# Smarttree_CMU_5_2_3.net
KiCad netlist of a schematic drawn in EAGLE
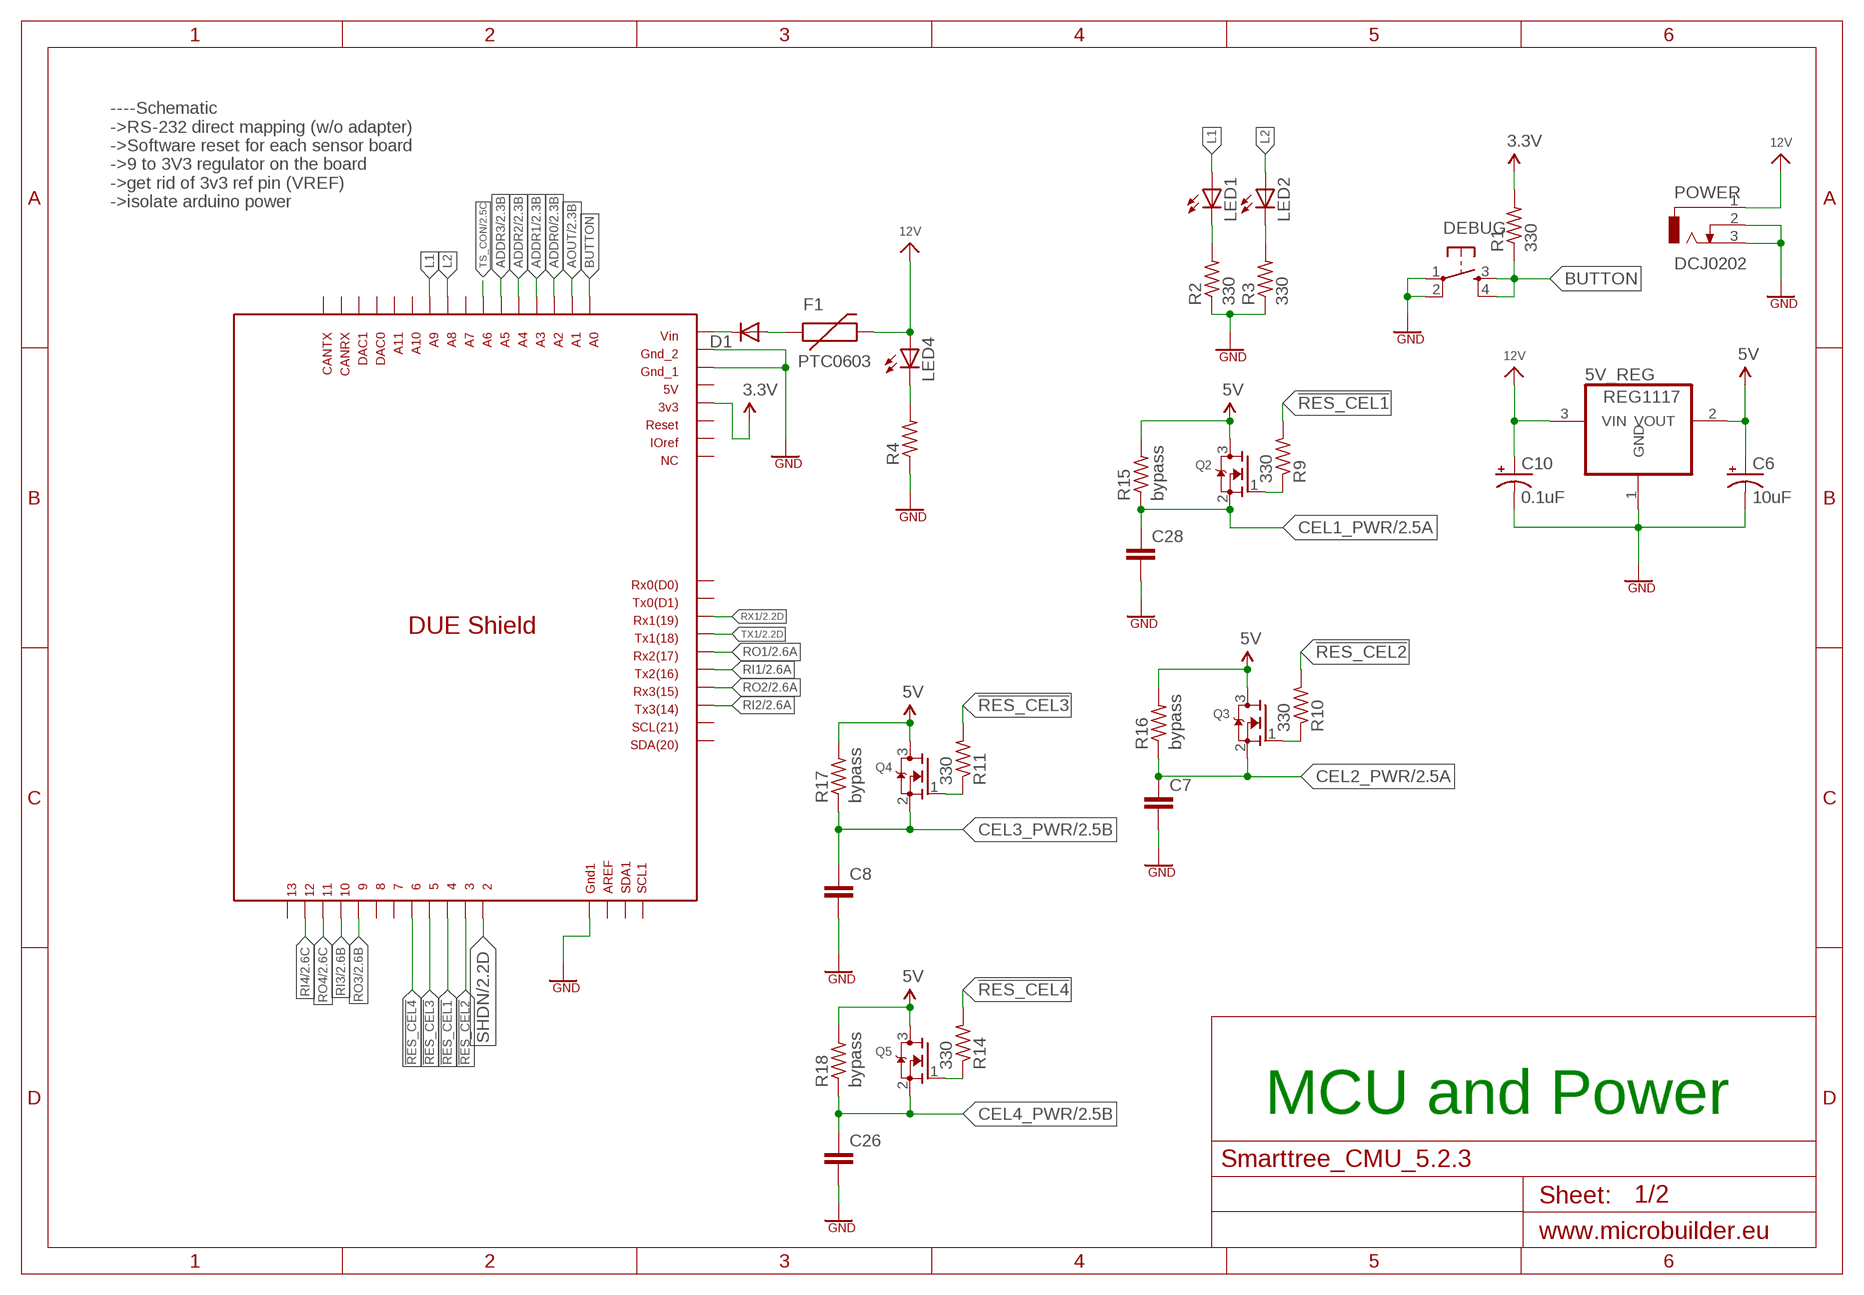
[diagram p0: schematic, sheet 1]
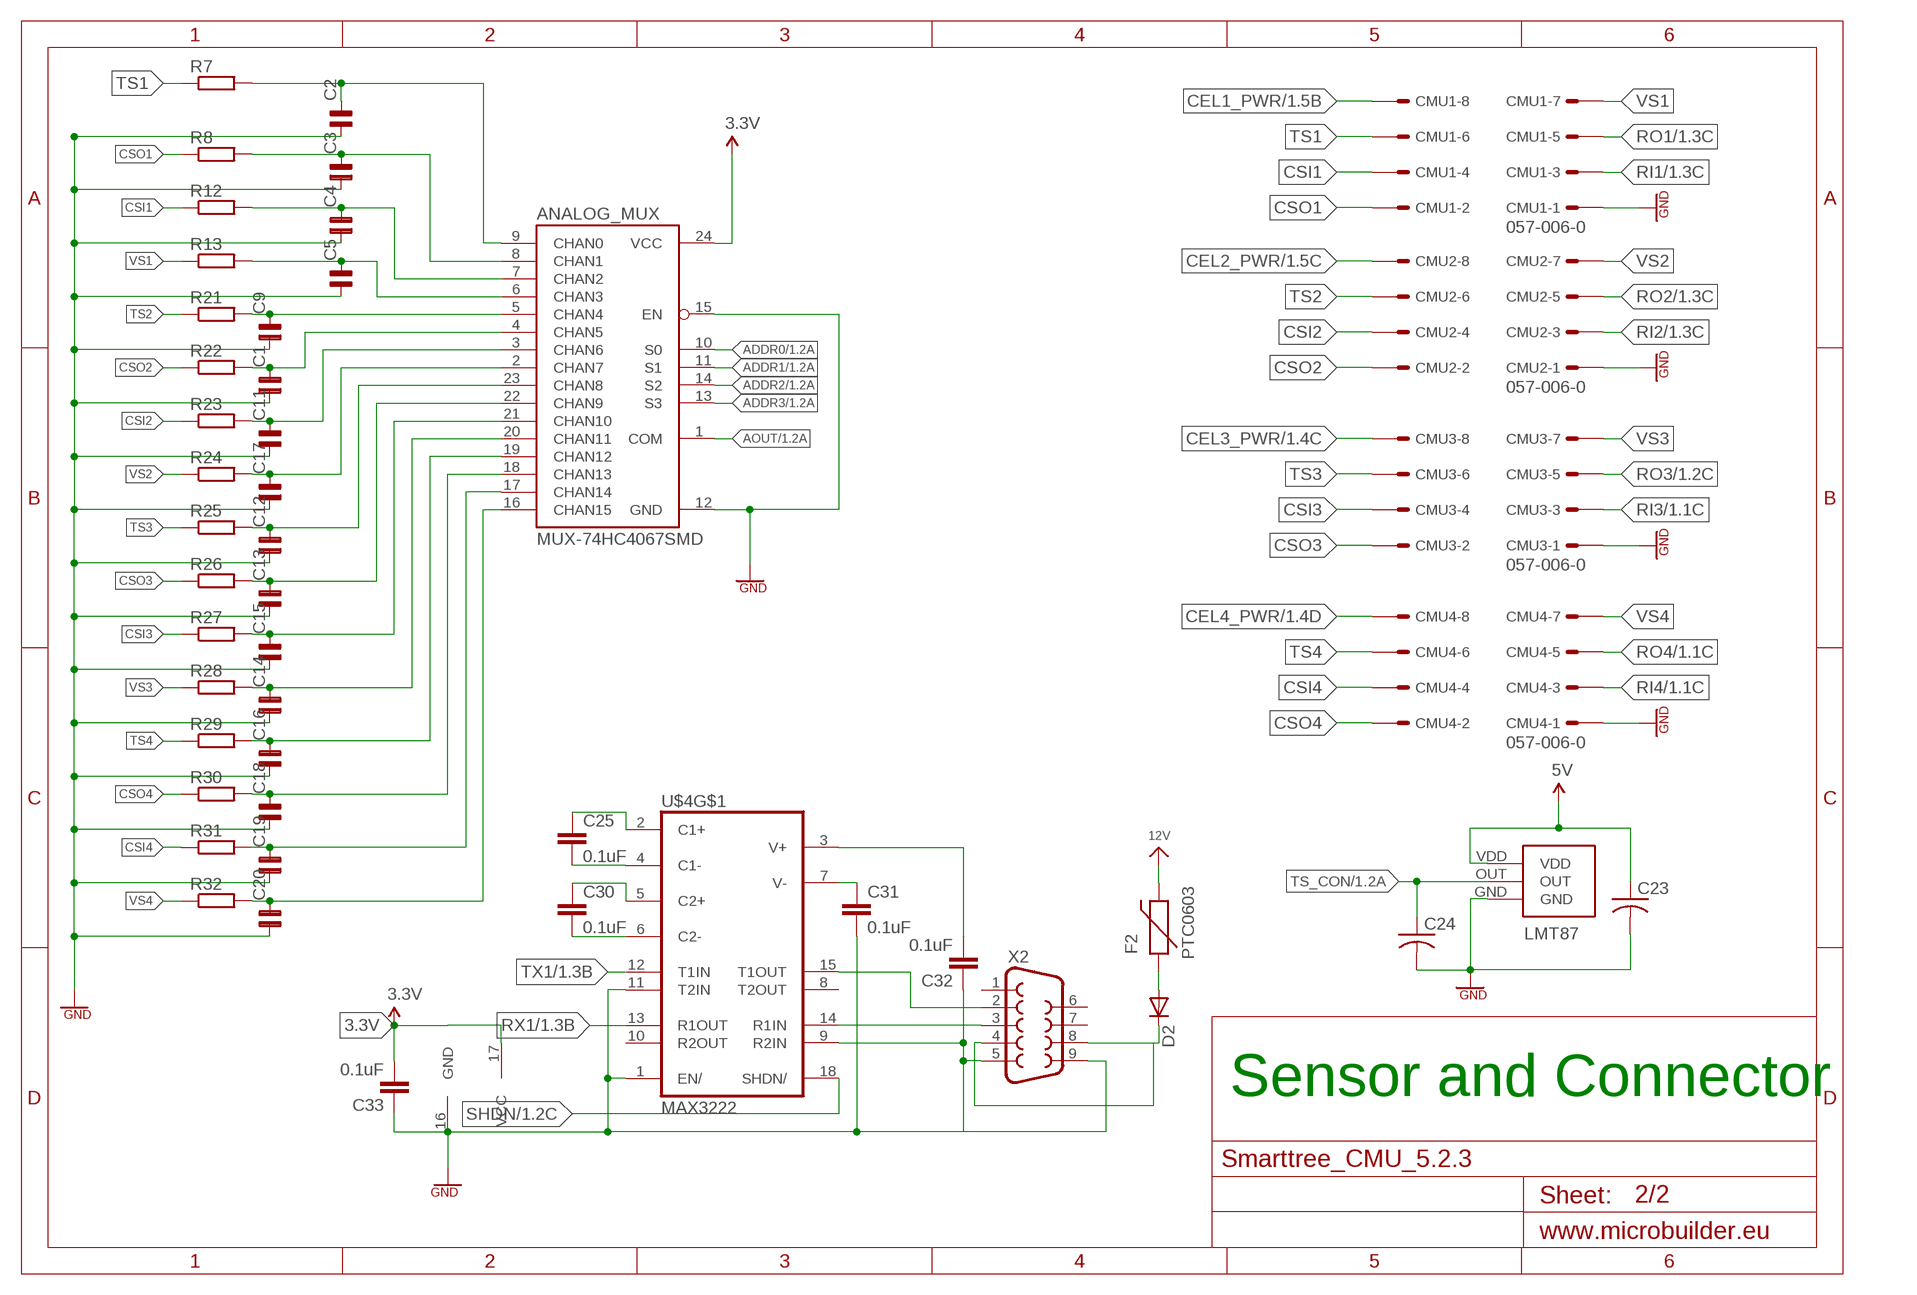
[diagram p1: schematic, sheet 2]

(export (version "E")
  (design (tool "Eeschema 10.0.6"))
  (components
    (comp (ref "5V_REG")
      (value "REG1117")
      (footprint "eagle-import:SOT223")
      (libsource (lib "eagle-import") (part "REG1117"))
    )
    (comp (ref "C6")
      (value "10uF")
      (footprint "eagle-import:EIA3216")
      (libsource (lib "eagle-import") (part "10UF-TANT"))
    )
    (comp (ref "C7")
      (value "CAP0603-CAP")
      (footprint "eagle-import:0603-CAP")
      (libsource (lib "eagle-import") (part "CAP0603-CAP"))
    )
    (comp (ref "C8")
      (value "CAP0603-CAP")
      (footprint "eagle-import:0603-CAP")
      (libsource (lib "eagle-import") (part "CAP0603-CAP"))
    )
    (comp (ref "C10")
      (value "0.1uF")
      (footprint "eagle-import:EIA3216")
      (libsource (lib "eagle-import") (part "10UF-TANT"))
    )
    (comp (ref "C26")
      (value "CAP0603-CAP")
      (footprint "eagle-import:0603-CAP")
      (libsource (lib "eagle-import") (part "CAP0603-CAP"))
    )
    (comp (ref "C28")
      (value "CAP0603-CAP")
      (footprint "eagle-import:0603-CAP")
      (libsource (lib "eagle-import") (part "CAP0603-CAP"))
    )
    (comp (ref "D1")
      (value "DIODE-SOD106-R")
      (footprint "eagle-import:SOD106-R")
      (libsource (lib "eagle-import") (part "DIODE-SOD106-R"))
    )
    (comp (ref "DEBUG")
      (value "TAC_SWITCHSMD")
      (footprint "eagle-import:TACTILE_SWITCH_SMD")
      (libsource (lib "eagle-import") (part "TAC_SWITCHSMD"))
    )
    (comp (ref "F1")
      (value "PTC0603")
      (footprint "eagle-import:0603")
      (libsource (lib "eagle-import") (part "PTC0603"))
    )
    (comp (ref "LED1")
      (value "LED-YELLOW0603")
      (footprint "eagle-import:LED-0603")
      (libsource (lib "eagle-import") (part "LED-YELLOW0603"))
    )
    (comp (ref "LED2")
      (value "LED-YELLOW0603")
      (footprint "eagle-import:LED-0603")
      (libsource (lib "eagle-import") (part "LED-YELLOW0603"))
    )
    (comp (ref "LED4")
      (value "LED-YELLOW0603")
      (footprint "eagle-import:LED-0603")
      (libsource (lib "eagle-import") (part "LED-YELLOW0603"))
    )
    (comp (ref "POWER")
      (value "DCJ0202")
      (footprint "eagle-import:DCJ0202")
      (libsource (lib "eagle-import") (part "DCJ0202"))
    )
    (comp (ref "Q2")
      (value "MOSFET-NREFLOW")
      (footprint "eagle-import:SOT23")
      (libsource (lib "eagle-import") (part "MOSFET-NREFLOW"))
    )
    (comp (ref "Q3")
      (value "MOSFET-NREFLOW")
      (footprint "eagle-import:SOT23")
      (libsource (lib "eagle-import") (part "MOSFET-NREFLOW"))
    )
    (comp (ref "Q4")
      (value "MOSFET-NREFLOW")
      (footprint "eagle-import:SOT23")
      (libsource (lib "eagle-import") (part "MOSFET-NREFLOW"))
    )
    (comp (ref "Q5")
      (value "MOSFET-NREFLOW")
      (footprint "eagle-import:SOT23")
      (libsource (lib "eagle-import") (part "MOSFET-NREFLOW"))
    )
    (comp (ref "R1")
      (value "330")
      (footprint "eagle-import:M0805")
      (libsource (lib "eagle-import") (part "R-US_M0805"))
    )
    (comp (ref "R2")
      (value "330")
      (footprint "eagle-import:M0805")
      (libsource (lib "eagle-import") (part "R-US_M0805"))
    )
    (comp (ref "R3")
      (value "330")
      (footprint "eagle-import:M0805")
      (libsource (lib "eagle-import") (part "R-US_M0805"))
    )
    (comp (ref "R4")
      (value "R-US_M0805")
      (footprint "eagle-import:M0805")
      (libsource (lib "eagle-import") (part "R-US_M0805"))
    )
    (comp (ref "R9")
      (value "330")
      (footprint "eagle-import:R0805")
      (libsource (lib "eagle-import") (part "R-US_R0805"))
    )
    (comp (ref "R10")
      (value "330")
      (footprint "eagle-import:R0805")
      (libsource (lib "eagle-import") (part "R-US_R0805"))
    )
    (comp (ref "R11")
      (value "330")
      (footprint "eagle-import:R0805")
      (libsource (lib "eagle-import") (part "R-US_R0805"))
    )
    (comp (ref "R14")
      (value "330")
      (footprint "eagle-import:R0805")
      (libsource (lib "eagle-import") (part "R-US_R0805"))
    )
    (comp (ref "R15")
      (value "bypass")
      (footprint "eagle-import:M0805")
      (libsource (lib "eagle-import") (part "R-US_M0805"))
    )
    (comp (ref "R16")
      (value "bypass")
      (footprint "eagle-import:M0805")
      (libsource (lib "eagle-import") (part "R-US_M0805"))
    )
    (comp (ref "R17")
      (value "bypass")
      (footprint "eagle-import:M0805")
      (libsource (lib "eagle-import") (part "R-US_M0805"))
    )
    (comp (ref "R18")
      (value "bypass")
      (footprint "eagle-import:M0805")
      (libsource (lib "eagle-import") (part "R-US_M0805"))
    )
    (comp (ref "U$1")
      (value "DUE(OUTLINE)")
      (footprint "eagle-import:DUE(NORMAL)")
      (libsource (lib "eagle-import") (part "DUE(OUTLINE)"))
    )
    (comp (ref "ANALOG_MUX")
      (value "MUX-74HC4067SMD")
      (footprint "eagle-import:SSOP24")
      (libsource (lib "eagle-import") (part "MUX-74HC4067SMD"))
    )
    (comp (ref "C1")
      (value "C-NP-SMD-0805")
      (footprint "eagle-import:C-0805")
      (libsource (lib "eagle-import") (part "C-NP-SMD-0805"))
    )
    (comp (ref "C2")
      (value "C-NP-SMD-0805")
      (footprint "eagle-import:C-0805")
      (libsource (lib "eagle-import") (part "C-NP-SMD-0805"))
    )
    (comp (ref "C3")
      (value "C-NP-SMD-0805")
      (footprint "eagle-import:C-0805")
      (libsource (lib "eagle-import") (part "C-NP-SMD-0805"))
    )
    (comp (ref "C4")
      (value "C-NP-SMD-0805")
      (footprint "eagle-import:C-0805")
      (libsource (lib "eagle-import") (part "C-NP-SMD-0805"))
    )
    (comp (ref "C5")
      (value "C-NP-SMD-0805")
      (footprint "eagle-import:C-0805")
      (libsource (lib "eagle-import") (part "C-NP-SMD-0805"))
    )
    (comp (ref "C9")
      (value "C-NP-SMD-0805")
      (footprint "eagle-import:C-0805")
      (libsource (lib "eagle-import") (part "C-NP-SMD-0805"))
    )
    (comp (ref "C11")
      (value "C-NP-SMD-0805")
      (footprint "eagle-import:C-0805")
      (libsource (lib "eagle-import") (part "C-NP-SMD-0805"))
    )
    (comp (ref "C12")
      (value "C-NP-SMD-0805")
      (footprint "eagle-import:C-0805")
      (libsource (lib "eagle-import") (part "C-NP-SMD-0805"))
    )
    (comp (ref "C13")
      (value "C-NP-SMD-0805")
      (footprint "eagle-import:C-0805")
      (libsource (lib "eagle-import") (part "C-NP-SMD-0805"))
    )
    (comp (ref "C14")
      (value "C-NP-SMD-0805")
      (footprint "eagle-import:C-0805")
      (libsource (lib "eagle-import") (part "C-NP-SMD-0805"))
    )
    (comp (ref "C15")
      (value "C-NP-SMD-0805")
      (footprint "eagle-import:C-0805")
      (libsource (lib "eagle-import") (part "C-NP-SMD-0805"))
    )
    (comp (ref "C16")
      (value "C-NP-SMD-0805")
      (footprint "eagle-import:C-0805")
      (libsource (lib "eagle-import") (part "C-NP-SMD-0805"))
    )
    (comp (ref "C17")
      (value "C-NP-SMD-0805")
      (footprint "eagle-import:C-0805")
      (libsource (lib "eagle-import") (part "C-NP-SMD-0805"))
    )
    (comp (ref "C18")
      (value "C-NP-SMD-0805")
      (footprint "eagle-import:C-0805")
      (libsource (lib "eagle-import") (part "C-NP-SMD-0805"))
    )
    (comp (ref "C19")
      (value "C-NP-SMD-0805")
      (footprint "eagle-import:C-0805")
      (libsource (lib "eagle-import") (part "C-NP-SMD-0805"))
    )
    (comp (ref "C20")
      (value "C-NP-SMD-0805")
      (footprint "eagle-import:C-0805")
      (libsource (lib "eagle-import") (part "C-NP-SMD-0805"))
    )
    (comp (ref "C23")
      (value "C-USC0805")
      (footprint "eagle-import:C0805")
      (libsource (lib "eagle-import") (part "C-USC0805"))
    )
    (comp (ref "C24")
      (value "C-USC0805")
      (footprint "eagle-import:C0805")
      (libsource (lib "eagle-import") (part "C-USC0805"))
    )
    (comp (ref "C25")
      (value "0.1uF")
      (footprint "eagle-import:0603-CAP")
      (libsource (lib "eagle-import") (part "CAP0603-CAP"))
    )
    (comp (ref "C30")
      (value "0.1uF")
      (footprint "eagle-import:0603-CAP")
      (libsource (lib "eagle-import") (part "CAP0603-CAP"))
    )
    (comp (ref "C31")
      (value "0.1uF")
      (footprint "eagle-import:0603-CAP")
      (libsource (lib "eagle-import") (part "CAP0603-CAP"))
    )
    (comp (ref "C32")
      (value "0.1uF")
      (footprint "eagle-import:0603-CAP")
      (libsource (lib "eagle-import") (part "CAP0603-CAP"))
    )
    (comp (ref "C33")
      (value "0.1uF")
      (footprint "eagle-import:0603-CAP")
      (libsource (lib "eagle-import") (part "CAP0603-CAP"))
    )
    (comp (ref "CMU1")
      (value "057-006-0")
      (footprint "eagle-import:057-006-0")
      (libsource (lib "eagle-import") (part "057-006-0"))
    )
    (comp (ref "CMU2")
      (value "057-006-0")
      (footprint "eagle-import:057-006-0")
      (libsource (lib "eagle-import") (part "057-006-0"))
    )
    (comp (ref "CMU3")
      (value "057-006-0")
      (footprint "eagle-import:057-006-0")
      (libsource (lib "eagle-import") (part "057-006-0"))
    )
    (comp (ref "CMU4")
      (value "057-006-0")
      (footprint "eagle-import:057-006-0")
      (libsource (lib "eagle-import") (part "057-006-0"))
    )
    (comp (ref "D2")
      (value "DIODE-SOD106-R")
      (footprint "eagle-import:SOD106-R")
      (libsource (lib "eagle-import") (part "DIODE-SOD106-R"))
    )
    (comp (ref "F2")
      (value "PTC0603")
      (footprint "eagle-import:0603")
      (libsource (lib "eagle-import") (part "PTC0603"))
    )
    (comp (ref "LMT87")
      (value "LMT87_PAC")
      (footprint "eagle-import:LMT87_TO")
      (libsource (lib "eagle-import") (part "LMT87_PAC"))
    )
    (comp (ref "R7")
      (value "R-EU_R0805W")
      (footprint "eagle-import:R0805W")
      (libsource (lib "eagle-import") (part "R-EU_R0805W"))
    )
    (comp (ref "R8")
      (value "R-EU_R0805W")
      (footprint "eagle-import:R0805W")
      (libsource (lib "eagle-import") (part "R-EU_R0805W"))
    )
    (comp (ref "R12")
      (value "R-EU_R0805W")
      (footprint "eagle-import:R0805W")
      (libsource (lib "eagle-import") (part "R-EU_R0805W"))
    )
    (comp (ref "R13")
      (value "R-EU_R0805W")
      (footprint "eagle-import:R0805W")
      (libsource (lib "eagle-import") (part "R-EU_R0805W"))
    )
    (comp (ref "R21")
      (value "R-EU_R0805W")
      (footprint "eagle-import:R0805W")
      (libsource (lib "eagle-import") (part "R-EU_R0805W"))
    )
    (comp (ref "R22")
      (value "R-EU_R0805W")
      (footprint "eagle-import:R0805W")
      (libsource (lib "eagle-import") (part "R-EU_R0805W"))
    )
    (comp (ref "R23")
      (value "R-EU_R0805W")
      (footprint "eagle-import:R0805W")
      (libsource (lib "eagle-import") (part "R-EU_R0805W"))
    )
    (comp (ref "R24")
      (value "R-EU_R0805W")
      (footprint "eagle-import:R0805W")
      (libsource (lib "eagle-import") (part "R-EU_R0805W"))
    )
    (comp (ref "R25")
      (value "R-EU_R0805W")
      (footprint "eagle-import:R0805W")
      (libsource (lib "eagle-import") (part "R-EU_R0805W"))
    )
    (comp (ref "R26")
      (value "R-EU_R0805W")
      (footprint "eagle-import:R0805W")
      (libsource (lib "eagle-import") (part "R-EU_R0805W"))
    )
    (comp (ref "R27")
      (value "R-EU_R0805W")
      (footprint "eagle-import:R0805W")
      (libsource (lib "eagle-import") (part "R-EU_R0805W"))
    )
    (comp (ref "R28")
      (value "R-EU_R0805W")
      (footprint "eagle-import:R0805W")
      (libsource (lib "eagle-import") (part "R-EU_R0805W"))
    )
    (comp (ref "R29")
      (value "R-EU_R0805W")
      (footprint "eagle-import:R0805W")
      (libsource (lib "eagle-import") (part "R-EU_R0805W"))
    )
    (comp (ref "R30")
      (value "R-EU_R0805W")
      (footprint "eagle-import:R0805W")
      (libsource (lib "eagle-import") (part "R-EU_R0805W"))
    )
    (comp (ref "R31")
      (value "R-EU_R0805W")
      (footprint "eagle-import:R0805W")
      (libsource (lib "eagle-import") (part "R-EU_R0805W"))
    )
    (comp (ref "R32")
      (value "R-EU_R0805W")
      (footprint "eagle-import:R0805W")
      (libsource (lib "eagle-import") (part "R-EU_R0805W"))
    )
    (comp (ref "U$4")
      (value "MAX3222")
      (footprint "eagle-import:SO18")
      (libsource (lib "eagle-import") (part "MAX3222"))
    )
    (comp (ref "X2")
      (value "DB9MALE")
      (footprint "eagle-import:DB9_MALE")
      (libsource (lib "eagle-import") (part "DB9MALE"))
    )
  )
  (nets
    (net (code "1") (name "3.3V") (class "Default")
      (node (ref "ANALOG_MUX") (pin "24") (pinfunction "VCC_24") (pintype "bidirectional"))
      (node (ref "C33") (pin "2") (pinfunction "2_2") (pintype "passive"))
      (node (ref "R1") (pin "2") (pinfunction "2_2") (pintype "passive"))
      (node (ref "U$1") (pin "3V3") (pinfunction "3V3_3V3") (pintype "bidirectional"))
      (node (ref "U$4") (pin "17") (pinfunction "VCC_17") (pintype "bidirectional"))
    )
    (net (code "2") (name "5V") (class "Default")
      (node (ref "5V_REG") (pin "2") (pinfunction "VOUT_2") (pintype "output"))
      (node (ref "C23") (pin "1") (pinfunction "1_1") (pintype "passive"))
      (node (ref "C6") (pin "A") (pinfunction "+_A") (pintype "passive"))
      (node (ref "LMT87") (pin "VDD") (pinfunction "VDD_VDD") (pintype "bidirectional"))
      (node (ref "Q2") (pin "3") (pinfunction "D_3") (pintype "bidirectional"))
      (node (ref "Q3") (pin "3") (pinfunction "D_3") (pintype "bidirectional"))
      (node (ref "Q4") (pin "3") (pinfunction "D_3") (pintype "bidirectional"))
      (node (ref "Q5") (pin "3") (pinfunction "D_3") (pintype "bidirectional"))
      (node (ref "R15") (pin "2") (pinfunction "2_2") (pintype "passive"))
      (node (ref "R16") (pin "2") (pinfunction "2_2") (pintype "passive"))
      (node (ref "R17") (pin "2") (pinfunction "2_2") (pintype "passive"))
      (node (ref "R18") (pin "2") (pinfunction "2_2") (pintype "passive"))
    )
    (net (code "3") (name "12V") (class "Default")
      (node (ref "5V_REG") (pin "3") (pinfunction "VIN_3") (pintype "input"))
      (node (ref "C10") (pin "A") (pinfunction "+_A") (pintype "passive"))
      (node (ref "F1") (pin "2") (pinfunction "2_2") (pintype "bidirectional"))
      (node (ref "F2") (pin "2") (pinfunction "2_2") (pintype "bidirectional"))
      (node (ref "LED4") (pin "A") (pinfunction "A_A") (pintype "passive"))
      (node (ref "POWER") (pin "1") (pinfunction "1_1") (pintype "passive"))
    )
    (net (code "4") (name "ADDR0") (class "Default")
      (node (ref "ANALOG_MUX") (pin "10") (pinfunction "S0_10") (pintype "input"))
      (node (ref "U$1") (pin "A2") (pinfunction "A2_A2") (pintype "bidirectional"))
    )
    (net (code "5") (name "ADDR1") (class "Default")
      (node (ref "ANALOG_MUX") (pin "11") (pinfunction "S1_11") (pintype "input"))
      (node (ref "U$1") (pin "A3") (pinfunction "A3_A3") (pintype "bidirectional"))
    )
    (net (code "6") (name "ADDR2") (class "Default")
      (node (ref "ANALOG_MUX") (pin "14") (pinfunction "S2_14") (pintype "input"))
      (node (ref "U$1") (pin "A4") (pinfunction "A4_A4") (pintype "bidirectional"))
    )
    (net (code "7") (name "ADDR3") (class "Default")
      (node (ref "ANALOG_MUX") (pin "13") (pinfunction "S3_13") (pintype "input"))
      (node (ref "U$1") (pin "A5") (pinfunction "A5_A5") (pintype "bidirectional"))
    )
    (net (code "8") (name "AOUT") (class "Default")
      (node (ref "ANALOG_MUX") (pin "1") (pinfunction "COM_1") (pintype "bidirectional"))
      (node (ref "U$1") (pin "A1") (pinfunction "A1_A1") (pintype "bidirectional"))
    )
    (net (code "9") (name "BUTTON") (class "Default")
      (node (ref "DEBUG") (pin "3") (pinfunction "3_3") (pintype "passive"))
      (node (ref "DEBUG") (pin "4") (pinfunction "4_4") (pintype "passive"))
      (node (ref "R1") (pin "1") (pinfunction "1_1") (pintype "passive"))
      (node (ref "U$1") (pin "A0") (pinfunction "A0_A0") (pintype "bidirectional"))
    )
    (net (code "10") (name "CEL1_PWR") (class "Default")
      (node (ref "C28") (pin "1") (pinfunction "1_1") (pintype "passive"))
      (node (ref "CMU1") (pin "7") (pinfunction "S_7") (pintype "passive"))
      (node (ref "Q2") (pin "2") (pinfunction "S_2") (pintype "bidirectional"))
      (node (ref "R15") (pin "1") (pinfunction "1_1") (pintype "passive"))
    )
    (net (code "11") (name "CEL2_PWR") (class "Default")
      (node (ref "C7") (pin "1") (pinfunction "1_1") (pintype "passive"))
      (node (ref "CMU2") (pin "7") (pinfunction "S_7") (pintype "passive"))
      (node (ref "Q3") (pin "2") (pinfunction "S_2") (pintype "bidirectional"))
      (node (ref "R16") (pin "1") (pinfunction "1_1") (pintype "passive"))
    )
    (net (code "12") (name "CEL3_PWR") (class "Default")
      (node (ref "C8") (pin "1") (pinfunction "1_1") (pintype "passive"))
      (node (ref "CMU3") (pin "7") (pinfunction "S_7") (pintype "passive"))
      (node (ref "Q4") (pin "2") (pinfunction "S_2") (pintype "bidirectional"))
      (node (ref "R17") (pin "1") (pinfunction "1_1") (pintype "passive"))
    )
    (net (code "13") (name "CEL4_PWR") (class "Default")
      (node (ref "C26") (pin "1") (pinfunction "1_1") (pintype "passive"))
      (node (ref "CMU4") (pin "7") (pinfunction "S_7") (pintype "passive"))
      (node (ref "Q5") (pin "2") (pinfunction "S_2") (pintype "bidirectional"))
      (node (ref "R18") (pin "1") (pinfunction "1_1") (pintype "passive"))
    )
    (net (code "14") (name "CSI1") (class "Default")
      (node (ref "CMU1") (pin "4") (pinfunction "S_4") (pintype "passive"))
      (node (ref "R12") (pin "1") (pinfunction "1_1") (pintype "passive"))
    )
    (net (code "15") (name "CSI2") (class "Default")
      (node (ref "CMU2") (pin "4") (pinfunction "S_4") (pintype "passive"))
      (node (ref "R23") (pin "1") (pinfunction "1_1") (pintype "passive"))
    )
    (net (code "16") (name "CSI3") (class "Default")
      (node (ref "CMU3") (pin "4") (pinfunction "S_4") (pintype "passive"))
      (node (ref "R27") (pin "1") (pinfunction "1_1") (pintype "passive"))
    )
    (net (code "17") (name "CSI4") (class "Default")
      (node (ref "CMU4") (pin "4") (pinfunction "S_4") (pintype "passive"))
      (node (ref "R31") (pin "1") (pinfunction "1_1") (pintype "passive"))
    )
    (net (code "18") (name "CSO1") (class "Default")
      (node (ref "CMU1") (pin "2") (pinfunction "S_2") (pintype "passive"))
      (node (ref "R8") (pin "1") (pinfunction "1_1") (pintype "passive"))
    )
    (net (code "19") (name "CSO2") (class "Default")
      (node (ref "CMU2") (pin "2") (pinfunction "S_2") (pintype "passive"))
      (node (ref "R22") (pin "1") (pinfunction "1_1") (pintype "passive"))
    )
    (net (code "20") (name "CSO3") (class "Default")
      (node (ref "CMU3") (pin "2") (pinfunction "S_2") (pintype "passive"))
      (node (ref "R26") (pin "1") (pinfunction "1_1") (pintype "passive"))
    )
    (net (code "21") (name "CSO4") (class "Default")
      (node (ref "CMU4") (pin "2") (pinfunction "S_2") (pintype "passive"))
      (node (ref "R30") (pin "1") (pinfunction "1_1") (pintype "passive"))
    )
    (net (code "22") (name "GND") (class "Default")
      (node (ref "5V_REG") (pin "1") (pinfunction "GND_1") (pintype "power_in"))
      (node (ref "ANALOG_MUX") (pin "12") (pinfunction "GND_12") (pintype "bidirectional"))
      (node (ref "ANALOG_MUX") (pin "15") (pinfunction "EN_15") (pintype "input"))
      (node (ref "C1") (pin "1") (pinfunction "1_1") (pintype "passive"))
      (node (ref "C10") (pin "C") (pinfunction "-_C") (pintype "passive"))
      (node (ref "C11") (pin "1") (pinfunction "1_1") (pintype "passive"))
      (node (ref "C12") (pin "1") (pinfunction "1_1") (pintype "passive"))
      (node (ref "C13") (pin "1") (pinfunction "1_1") (pintype "passive"))
      (node (ref "C14") (pin "1") (pinfunction "1_1") (pintype "passive"))
      (node (ref "C15") (pin "1") (pinfunction "1_1") (pintype "passive"))
      (node (ref "C16") (pin "1") (pinfunction "1_1") (pintype "passive"))
      (node (ref "C17") (pin "1") (pinfunction "1_1") (pintype "passive"))
      (node (ref "C18") (pin "1") (pinfunction "1_1") (pintype "passive"))
      (node (ref "C19") (pin "1") (pinfunction "1_1") (pintype "passive"))
      (node (ref "C2") (pin "1") (pinfunction "1_1") (pintype "passive"))
      (node (ref "C20") (pin "1") (pinfunction "1_1") (pintype "passive"))
      (node (ref "C23") (pin "2") (pinfunction "2_2") (pintype "passive"))
      (node (ref "C24") (pin "2") (pinfunction "2_2") (pintype "passive"))
      (node (ref "C26") (pin "2") (pinfunction "2_2") (pintype "passive"))
      (node (ref "C28") (pin "2") (pinfunction "2_2") (pintype "passive"))
      (node (ref "C3") (pin "1") (pinfunction "1_1") (pintype "passive"))
      (node (ref "C31") (pin "2") (pinfunction "2_2") (pintype "passive"))
      (node (ref "C32") (pin "1") (pinfunction "1_1") (pintype "passive"))
      (node (ref "C33") (pin "1") (pinfunction "1_1") (pintype "passive"))
      (node (ref "C4") (pin "1") (pinfunction "1_1") (pintype "passive"))
      (node (ref "C5") (pin "1") (pinfunction "1_1") (pintype "passive"))
      (node (ref "C6") (pin "C") (pinfunction "-_C") (pintype "passive"))
      (node (ref "C7") (pin "2") (pinfunction "2_2") (pintype "passive"))
      (node (ref "C8") (pin "2") (pinfunction "2_2") (pintype "passive"))
      (node (ref "C9") (pin "1") (pinfunction "1_1") (pintype "passive"))
      (node (ref "CMU1") (pin "1") (pinfunction "S_1") (pintype "passive"))
      (node (ref "CMU2") (pin "1") (pinfunction "S_1") (pintype "passive"))
      (node (ref "CMU3") (pin "1") (pinfunction "S_1") (pintype "passive"))
      (node (ref "CMU4") (pin "1") (pinfunction "S_1") (pintype "passive"))
      (node (ref "DEBUG") (pin "1") (pinfunction "1_1") (pintype "passive"))
      (node (ref "DEBUG") (pin "2") (pinfunction "2_2") (pintype "passive"))
      (node (ref "LMT87") (pin "GND") (pinfunction "GND_GND") (pintype "bidirectional"))
      (node (ref "POWER") (pin "2") (pinfunction "2_2") (pintype "passive"))
      (node (ref "POWER") (pin "3") (pinfunction "3_3") (pintype "passive"))
      (node (ref "R2") (pin "1") (pinfunction "1_1") (pintype "passive"))
      (node (ref "R3") (pin "1") (pinfunction "1_1") (pintype "passive"))
      (node (ref "R4") (pin "1") (pinfunction "1_1") (pintype "passive"))
      (node (ref "U$1") (pin "GND1") (pinfunction "GND1_GND1") (pintype "bidirectional"))
      (node (ref "U$1") (pin "GND_1") (pinfunction "GND_1_GND_1") (pintype "bidirectional"))
      (node (ref "U$1") (pin "GND_2") (pinfunction "GND_2_GND_2") (pintype "bidirectional"))
      (node (ref "U$4") (pin "1") (pinfunction "EN/_1") (pintype "input"))
      (node (ref "U$4") (pin "11") (pinfunction "T2IN_11") (pintype "input"))
      (node (ref "U$4") (pin "16") (pinfunction "GND_16") (pintype "bidirectional"))
      (node (ref "U$4") (pin "9") (pinfunction "R2IN_9") (pintype "input"))
      (node (ref "X2") (pin "5") (pinfunction "5_5") (pintype "passive"))
      (node (ref "X2") (pin "9") (pinfunction "9_9") (pintype "passive"))
    )
    (net (code "23") (name "L1") (class "Default")
      (node (ref "LED1") (pin "A") (pinfunction "A_A") (pintype "passive"))
      (node (ref "U$1") (pin "A9") (pinfunction "A9_A9") (pintype "bidirectional"))
    )
    (net (code "24") (name "L2") (class "Default")
      (node (ref "LED2") (pin "A") (pinfunction "A_A") (pintype "passive"))
      (node (ref "U$1") (pin "A8") (pinfunction "A8_A8") (pintype "bidirectional"))
    )
    (net (code "25") (name "Net-(ANALOG_MUX-CHAN0)") (class "Default")
      (node (ref "ANALOG_MUX") (pin "9") (pinfunction "CHAN0_9") (pintype "bidirectional"))
      (node (ref "C2") (pin "2") (pinfunction "2_2") (pintype "passive"))
      (node (ref "R7") (pin "2") (pinfunction "2_2") (pintype "passive"))
    )
    (net (code "26") (name "Net-(ANALOG_MUX-CHAN1)") (class "Default")
      (node (ref "ANALOG_MUX") (pin "8") (pinfunction "CHAN1_8") (pintype "bidirectional"))
      (node (ref "C3") (pin "2") (pinfunction "2_2") (pintype "passive"))
      (node (ref "R8") (pin "2") (pinfunction "2_2") (pintype "passive"))
    )
    (net (code "27") (name "Net-(ANALOG_MUX-CHAN2)") (class "Default")
      (node (ref "ANALOG_MUX") (pin "7") (pinfunction "CHAN2_7") (pintype "bidirectional"))
      (node (ref "C4") (pin "2") (pinfunction "2_2") (pintype "passive"))
      (node (ref "R12") (pin "2") (pinfunction "2_2") (pintype "passive"))
    )
    (net (code "28") (name "Net-(ANALOG_MUX-CHAN3)") (class "Default")
      (node (ref "ANALOG_MUX") (pin "6") (pinfunction "CHAN3_6") (pintype "bidirectional"))
      (node (ref "C5") (pin "2") (pinfunction "2_2") (pintype "passive"))
      (node (ref "R13") (pin "2") (pinfunction "2_2") (pintype "passive"))
    )
    (net (code "29") (name "Net-(ANALOG_MUX-CHAN4)") (class "Default")
      (node (ref "ANALOG_MUX") (pin "5") (pinfunction "CHAN4_5") (pintype "bidirectional"))
      (node (ref "C9") (pin "2") (pinfunction "2_2") (pintype "passive"))
      (node (ref "R21") (pin "2") (pinfunction "2_2") (pintype "passive"))
    )
    (net (code "30") (name "Net-(ANALOG_MUX-CHAN5)") (class "Default")
      (node (ref "ANALOG_MUX") (pin "4") (pinfunction "CHAN5_4") (pintype "bidirectional"))
      (node (ref "C1") (pin "2") (pinfunction "2_2") (pintype "passive"))
      (node (ref "R22") (pin "2") (pinfunction "2_2") (pintype "passive"))
    )
    (net (code "31") (name "Net-(ANALOG_MUX-CHAN6)") (class "Default")
      (node (ref "ANALOG_MUX") (pin "3") (pinfunction "CHAN6_3") (pintype "bidirectional"))
      (node (ref "C11") (pin "2") (pinfunction "2_2") (pintype "passive"))
      (node (ref "R23") (pin "2") (pinfunction "2_2") (pintype "passive"))
    )
    (net (code "32") (name "Net-(ANALOG_MUX-CHAN7)") (class "Default")
      (node (ref "ANALOG_MUX") (pin "2") (pinfunction "CHAN7_2") (pintype "bidirectional"))
      (node (ref "C17") (pin "2") (pinfunction "2_2") (pintype "passive"))
      (node (ref "R24") (pin "2") (pinfunction "2_2") (pintype "passive"))
    )
    (net (code "33") (name "Net-(ANALOG_MUX-CHAN8)") (class "Default")
      (node (ref "ANALOG_MUX") (pin "23") (pinfunction "CHAN8_23") (pintype "bidirectional"))
      (node (ref "C12") (pin "2") (pinfunction "2_2") (pintype "passive"))
      (node (ref "R25") (pin "2") (pinfunction "2_2") (pintype "passive"))
    )
    (net (code "34") (name "Net-(ANALOG_MUX-CHAN9)") (class "Default")
      (node (ref "ANALOG_MUX") (pin "22") (pinfunction "CHAN9_22") (pintype "bidirectional"))
      (node (ref "C13") (pin "2") (pinfunction "2_2") (pintype "passive"))
      (node (ref "R26") (pin "2") (pinfunction "2_2") (pintype "passive"))
    )
    (net (code "35") (name "Net-(ANALOG_MUX-CHAN10)") (class "Default")
      (node (ref "ANALOG_MUX") (pin "21") (pinfunction "CHAN10_21") (pintype "bidirectional"))
      (node (ref "C15") (pin "2") (pinfunction "2_2") (pintype "passive"))
      (node (ref "R27") (pin "2") (pinfunction "2_2") (pintype "passive"))
    )
    (net (code "36") (name "Net-(ANALOG_MUX-CHAN11)") (class "Default")
      (node (ref "ANALOG_MUX") (pin "20") (pinfunction "CHAN11_20") (pintype "bidirectional"))
      (node (ref "C14") (pin "2") (pinfunction "2_2") (pintype "passive"))
      (node (ref "R28") (pin "2") (pinfunction "2_2") (pintype "passive"))
    )
    (net (code "37") (name "Net-(ANALOG_MUX-CHAN12)") (class "Default")
      (node (ref "ANALOG_MUX") (pin "19") (pinfunction "CHAN12_19") (pintype "bidirectional"))
      (node (ref "C16") (pin "2") (pinfunction "2_2") (pintype "passive"))
      (node (ref "R29") (pin "2") (pinfunction "2_2") (pintype "passive"))
    )
    (net (code "38") (name "Net-(ANALOG_MUX-CHAN13)") (class "Default")
      (node (ref "ANALOG_MUX") (pin "18") (pinfunction "CHAN13_18") (pintype "bidirectional"))
      (node (ref "C18") (pin "2") (pinfunction "2_2") (pintype "passive"))
      (node (ref "R30") (pin "2") (pinfunction "2_2") (pintype "passive"))
    )
    (net (code "39") (name "Net-(ANALOG_MUX-CHAN14)") (class "Default")
      (node (ref "ANALOG_MUX") (pin "17") (pinfunction "CHAN14_17") (pintype "bidirectional"))
      (node (ref "C19") (pin "2") (pinfunction "2_2") (pintype "passive"))
      (node (ref "R31") (pin "2") (pinfunction "2_2") (pintype "passive"))
    )
    (net (code "40") (name "Net-(ANALOG_MUX-CHAN15)") (class "Default")
      (node (ref "ANALOG_MUX") (pin "16") (pinfunction "CHAN15_16") (pintype "bidirectional"))
      (node (ref "C20") (pin "2") (pinfunction "2_2") (pintype "passive"))
      (node (ref "R32") (pin "2") (pinfunction "2_2") (pintype "passive"))
    )
    (net (code "41") (name "Net-(D1-PadA)") (class "Default")
      (node (ref "D1") (pin "A") (pinfunction "A_A") (pintype "passive"))
      (node (ref "F1") (pin "1") (pinfunction "1_1") (pintype "bidirectional"))
    )
    (net (code "42") (name "Net-(D1-PadC)") (class "Default")
      (node (ref "D1") (pin "C") (pinfunction "C_C") (pintype "passive"))
      (node (ref "U$1") (pin "VIN") (pinfunction "VIN_VIN") (pintype "bidirectional"))
    )
    (net (code "43") (name "Net-(D2-PadA)") (class "Default")
      (node (ref "D2") (pin "A") (pinfunction "A_A") (pintype "passive"))
      (node (ref "F2") (pin "1") (pinfunction "1_1") (pintype "bidirectional"))
    )
    (net (code "44") (name "Net-(D2-PadC)") (class "Default")
      (node (ref "D2") (pin "C") (pinfunction "C_C") (pintype "passive"))
      (node (ref "X2") (pin "4") (pinfunction "4_4") (pintype "passive"))
      (node (ref "X2") (pin "8") (pinfunction "8_8") (pintype "passive"))
    )
    (net (code "45") (name "Net-(LED1-PadC)") (class "Default")
      (node (ref "LED1") (pin "C") (pinfunction "C_C") (pintype "passive"))
      (node (ref "R2") (pin "2") (pinfunction "2_2") (pintype "passive"))
    )
    (net (code "46") (name "Net-(LED2-PadC)") (class "Default")
      (node (ref "LED2") (pin "C") (pinfunction "C_C") (pintype "passive"))
      (node (ref "R3") (pin "2") (pinfunction "2_2") (pintype "passive"))
    )
    (net (code "47") (name "Net-(LED4-PadC)") (class "Default")
      (node (ref "LED4") (pin "C") (pinfunction "C_C") (pintype "passive"))
      (node (ref "R4") (pin "2") (pinfunction "2_2") (pintype "passive"))
    )
    (net (code "48") (name "Net-(Q2-G)") (class "Default")
      (node (ref "Q2") (pin "1") (pinfunction "G_1") (pintype "bidirectional"))
      (node (ref "R9") (pin "1") (pinfunction "1_1") (pintype "passive"))
    )
    (net (code "49") (name "Net-(Q3-G)") (class "Default")
      (node (ref "Q3") (pin "1") (pinfunction "G_1") (pintype "bidirectional"))
      (node (ref "R10") (pin "1") (pinfunction "1_1") (pintype "passive"))
    )
    (net (code "50") (name "Net-(Q4-G)") (class "Default")
      (node (ref "Q4") (pin "1") (pinfunction "G_1") (pintype "bidirectional"))
      (node (ref "R11") (pin "1") (pinfunction "1_1") (pintype "passive"))
    )
    (net (code "51") (name "Net-(Q5-G)") (class "Default")
      (node (ref "Q5") (pin "1") (pinfunction "G_1") (pintype "bidirectional"))
      (node (ref "R14") (pin "1") (pinfunction "1_1") (pintype "passive"))
    )
    (net (code "52") (name "Net-(U$4A-C1+)") (class "Default")
      (node (ref "C25") (pin "1") (pinfunction "1_1") (pintype "passive"))
      (node (ref "U$4") (pin "2") (pinfunction "C1+_2") (pintype "passive"))
    )
    (net (code "53") (name "Net-(U$4A-C1-)") (class "Default")
      (node (ref "C25") (pin "2") (pinfunction "2_2") (pintype "passive"))
      (node (ref "U$4") (pin "4") (pinfunction "C1-_4") (pintype "passive"))
    )
    (net (code "54") (name "Net-(U$4A-C2+)") (class "Default")
      (node (ref "C30") (pin "1") (pinfunction "1_1") (pintype "passive"))
      (node (ref "U$4") (pin "5") (pinfunction "C2+_5") (pintype "passive"))
    )
    (net (code "55") (name "Net-(U$4A-C2-)") (class "Default")
      (node (ref "C30") (pin "2") (pinfunction "2_2") (pintype "passive"))
      (node (ref "U$4") (pin "6") (pinfunction "C2-_6") (pintype "passive"))
    )
    (net (code "56") (name "Net-(U$4A-R1IN)") (class "Default")
      (node (ref "U$4") (pin "14") (pinfunction "R1IN_14") (pintype "input"))
      (node (ref "X2") (pin "3") (pinfunction "3_3") (pintype "passive"))
    )
    (net (code "57") (name "Net-(U$4A-T1OUT)") (class "Default")
      (node (ref "U$4") (pin "15") (pinfunction "T1OUT_15") (pintype "output"))
      (node (ref "X2") (pin "2") (pinfunction "2_2") (pintype "passive"))
    )
    (net (code "58") (name "Net-(U$4A-V+)") (class "Default")
      (node (ref "C32") (pin "2") (pinfunction "2_2") (pintype "passive"))
      (node (ref "U$4") (pin "3") (pinfunction "V+_3") (pintype "passive"))
    )
    (net (code "59") (name "Net-(U$4A-V-)") (class "Default")
      (node (ref "C31") (pin "1") (pinfunction "1_1") (pintype "passive"))
      (node (ref "U$4") (pin "7") (pinfunction "V-_7") (pintype "passive"))
    )
    (net (code "60") (name "RI1") (class "Default")
      (node (ref "CMU1") (pin "3") (pinfunction "S_3") (pintype "passive"))
      (node (ref "U$1") (pin "TX2") (pinfunction "TX2_TX2") (pintype "bidirectional"))
    )
    (net (code "61") (name "RI2") (class "Default")
      (node (ref "CMU2") (pin "3") (pinfunction "S_3") (pintype "passive"))
      (node (ref "U$1") (pin "TX3") (pinfunction "TX3_TX3") (pintype "bidirectional"))
    )
    (net (code "62") (name "RI3") (class "Default")
      (node (ref "CMU3") (pin "3") (pinfunction "S_3") (pintype "passive"))
      (node (ref "U$1") (pin "10") (pinfunction "10_10") (pintype "bidirectional"))
    )
    (net (code "63") (name "RI4") (class "Default")
      (node (ref "CMU4") (pin "3") (pinfunction "S_3") (pintype "passive"))
      (node (ref "U$1") (pin "12") (pinfunction "12_12") (pintype "bidirectional"))
    )
    (net (code "64") (name "RO1") (class "Default")
      (node (ref "CMU1") (pin "5") (pinfunction "S_5") (pintype "passive"))
      (node (ref "U$1") (pin "RX2") (pinfunction "RX2_RX2") (pintype "bidirectional"))
    )
    (net (code "65") (name "RO2") (class "Default")
      (node (ref "CMU2") (pin "5") (pinfunction "S_5") (pintype "passive"))
      (node (ref "U$1") (pin "RX3") (pinfunction "RX3_RX3") (pintype "bidirectional"))
    )
    (net (code "66") (name "RO3") (class "Default")
      (node (ref "CMU3") (pin "5") (pinfunction "S_5") (pintype "passive"))
      (node (ref "U$1") (pin "9") (pinfunction "9_9") (pintype "bidirectional"))
    )
    (net (code "67") (name "RO4") (class "Default")
      (node (ref "CMU4") (pin "5") (pinfunction "S_5") (pintype "passive"))
      (node (ref "U$1") (pin "11") (pinfunction "11_11") (pintype "bidirectional"))
    )
    (net (code "68") (name "RX1") (class "Default")
      (node (ref "U$1") (pin "RX1") (pinfunction "RX1_RX1") (pintype "bidirectional"))
      (node (ref "U$4") (pin "13") (pinfunction "R1OUT_13") (pintype "output"))
    )
    (net (code "69") (name "SHDN") (class "Default")
      (node (ref "U$1") (pin "2") (pinfunction "2_2") (pintype "bidirectional"))
      (node (ref "U$4") (pin "18") (pinfunction "SHDN/_18") (pintype "input"))
    )
    (net (code "70") (name "TS1") (class "Default")
      (node (ref "CMU1") (pin "6") (pinfunction "S_6") (pintype "passive"))
      (node (ref "R7") (pin "1") (pinfunction "1_1") (pintype "passive"))
    )
    (net (code "71") (name "TS2") (class "Default")
      (node (ref "CMU2") (pin "6") (pinfunction "S_6") (pintype "passive"))
      (node (ref "R21") (pin "1") (pinfunction "1_1") (pintype "passive"))
    )
    (net (code "72") (name "TS3") (class "Default")
      (node (ref "CMU3") (pin "6") (pinfunction "S_6") (pintype "passive"))
      (node (ref "R25") (pin "1") (pinfunction "1_1") (pintype "passive"))
    )
    (net (code "73") (name "TS4") (class "Default")
      (node (ref "CMU4") (pin "6") (pinfunction "S_6") (pintype "passive"))
      (node (ref "R29") (pin "1") (pinfunction "1_1") (pintype "passive"))
    )
    (net (code "74") (name "TS_CON") (class "Default")
      (node (ref "C24") (pin "1") (pinfunction "1_1") (pintype "passive"))
      (node (ref "LMT87") (pin "OUT") (pinfunction "OUT_OUT") (pintype "bidirectional"))
      (node (ref "U$1") (pin "A6") (pinfunction "A6_A6") (pintype "bidirectional"))
    )
    (net (code "75") (name "TX1") (class "Default")
      (node (ref "U$1") (pin "TX1") (pinfunction "TX1_TX1") (pintype "bidirectional"))
      (node (ref "U$4") (pin "12") (pinfunction "T1IN_12") (pintype "input"))
    )
    (net (code "76") (name "VS1") (class "Default")
      (node (ref "CMU1") (pin "8") (pinfunction "S_8") (pintype "passive"))
      (node (ref "R13") (pin "1") (pinfunction "1_1") (pintype "passive"))
    )
    (net (code "77") (name "VS2") (class "Default")
      (node (ref "CMU2") (pin "8") (pinfunction "S_8") (pintype "passive"))
      (node (ref "R24") (pin "1") (pinfunction "1_1") (pintype "passive"))
    )
    (net (code "78") (name "VS3") (class "Default")
      (node (ref "CMU3") (pin "8") (pinfunction "S_8") (pintype "passive"))
      (node (ref "R28") (pin "1") (pinfunction "1_1") (pintype "passive"))
    )
    (net (code "79") (name "VS4") (class "Default")
      (node (ref "CMU4") (pin "8") (pinfunction "S_8") (pintype "passive"))
      (node (ref "R32") (pin "1") (pinfunction "1_1") (pintype "passive"))
    )
    (net (code "80") (name "unconnected-(U$1-Pad5V)") (class "Default")
      (node (ref "U$1") (pin "5V") (pinfunction "5V_5V") (pintype "bidirectional"))
    )
    (net (code "81") (name "unconnected-(U$1-Pad7)") (class "Default")
      (node (ref "U$1") (pin "7") (pinfunction "7_7") (pintype "bidirectional"))
    )
    (net (code "82") (name "unconnected-(U$1-Pad8)") (class "Default")
      (node (ref "U$1") (pin "8") (pinfunction "8_8") (pintype "bidirectional"))
    )
    (net (code "83") (name "unconnected-(U$1-Pad13)") (class "Default")
      (node (ref "U$1") (pin "13") (pinfunction "13_13") (pintype "bidirectional"))
    )
    (net (code "84") (name "unconnected-(U$1-PadA7)") (class "Default")
      (node (ref "U$1") (pin "A7") (pinfunction "A7_A7") (pintype "bidirectional"))
    )
    (net (code "85") (name "unconnected-(U$1-PadA10)") (class "Default")
      (node (ref "U$1") (pin "A10") (pinfunction "A10_A10") (pintype "bidirectional"))
    )
    (net (code "86") (name "unconnected-(U$1-PadA11)") (class "Default")
      (node (ref "U$1") (pin "A11") (pinfunction "A11_A11") (pintype "bidirectional"))
    )
    (net (code "87") (name "unconnected-(U$1-PadAREF)") (class "Default")
      (node (ref "U$1") (pin "AREF") (pinfunction "AREF_AREF") (pintype "bidirectional"))
    )
    (net (code "88") (name "unconnected-(U$1-PadCANRX)") (class "Default")
      (node (ref "U$1") (pin "CANRX") (pinfunction "CANRX_CANRX") (pintype "bidirectional"))
    )
    (net (code "89") (name "unconnected-(U$1-PadCANTX)") (class "Default")
      (node (ref "U$1") (pin "CANTX") (pinfunction "CANTX_CANTX") (pintype "bidirectional"))
    )
    (net (code "90") (name "unconnected-(U$1-PadDAC0)") (class "Default")
      (node (ref "U$1") (pin "DAC0") (pinfunction "DAC0_DAC0") (pintype "bidirectional"))
    )
    (net (code "91") (name "unconnected-(U$1-PadDAC1)") (class "Default")
      (node (ref "U$1") (pin "DAC1") (pinfunction "DAC1_DAC1") (pintype "bidirectional"))
    )
    (net (code "92") (name "unconnected-(U$1-PadIOREF)") (class "Default")
      (node (ref "U$1") (pin "IOREF") (pinfunction "IOREF_IOREF") (pintype "bidirectional"))
    )
    (net (code "93") (name "unconnected-(U$1-PadNC)") (class "Default")
      (node (ref "U$1") (pin "NC") (pinfunction "NC_NC") (pintype "bidirectional"))
    )
    (net (code "94") (name "unconnected-(U$1-PadRESET)") (class "Default")
      (node (ref "U$1") (pin "RESET") (pinfunction "RESET_RESET") (pintype "bidirectional"))
    )
    (net (code "95") (name "unconnected-(U$1-PadRX0)") (class "Default")
      (node (ref "U$1") (pin "RX0") (pinfunction "RX0_RX0") (pintype "bidirectional"))
    )
    (net (code "96") (name "unconnected-(U$1-PadSCL)") (class "Default")
      (node (ref "U$1") (pin "SCL") (pinfunction "SCL_SCL") (pintype "bidirectional"))
    )
    (net (code "97") (name "unconnected-(U$1-PadSCL1)") (class "Default")
      (node (ref "U$1") (pin "SCL1") (pinfunction "SCL1_SCL1") (pintype "bidirectional"))
    )
    (net (code "98") (name "unconnected-(U$1-PadSDA)") (class "Default")
      (node (ref "U$1") (pin "SDA") (pinfunction "SDA_SDA") (pintype "bidirectional"))
    )
    (net (code "99") (name "unconnected-(U$1-PadSDA1)") (class "Default")
      (node (ref "U$1") (pin "SDA1") (pinfunction "SDA1_SDA1") (pintype "bidirectional"))
    )
    (net (code "100") (name "unconnected-(U$1-PadTX0)") (class "Default")
      (node (ref "U$1") (pin "TX0") (pinfunction "TX0_TX0") (pintype "bidirectional"))
    )
    (net (code "101") (name "unconnected-(U$4A-R2OUT-Pad10)") (class "Default")
      (node (ref "U$4") (pin "10") (pinfunction "R2OUT_10") (pintype "output"))
    )
    (net (code "102") (name "unconnected-(U$4A-T2OUT-Pad8)") (class "Default")
      (node (ref "U$4") (pin "8") (pinfunction "T2OUT_8") (pintype "output"))
    )
    (net (code "103") (name "unconnected-(X2-Pad1)") (class "Default")
      (node (ref "X2") (pin "1") (pinfunction "1_1") (pintype "passive"))
    )
    (net (code "104") (name "unconnected-(X2-Pad6)") (class "Default")
      (node (ref "X2") (pin "6") (pinfunction "6_6") (pintype "passive"))
    )
    (net (code "105") (name "unconnected-(X2-Pad7)") (class "Default")
      (node (ref "X2") (pin "7") (pinfunction "7_7") (pintype "passive"))
    )
    (net (code "106") (name "~{RES_CEL1}") (class "Default")
      (node (ref "R9") (pin "2") (pinfunction "2_2") (pintype "passive"))
      (node (ref "U$1") (pin "4") (pinfunction "4_4") (pintype "bidirectional"))
    )
    (net (code "107") (name "~{RES_CEL2}") (class "Default")
      (node (ref "R10") (pin "2") (pinfunction "2_2") (pintype "passive"))
      (node (ref "U$1") (pin "3") (pinfunction "3_3") (pintype "bidirectional"))
    )
    (net (code "108") (name "~{RES_CEL3}") (class "Default")
      (node (ref "R11") (pin "2") (pinfunction "2_2") (pintype "passive"))
      (node (ref "U$1") (pin "5") (pinfunction "5_5") (pintype "bidirectional"))
    )
    (net (code "109") (name "~{RES_CEL4}") (class "Default")
      (node (ref "R14") (pin "2") (pinfunction "2_2") (pintype "passive"))
      (node (ref "U$1") (pin "6") (pinfunction "6_6") (pintype "bidirectional"))
    )
  )
)
